# in_out_mcp23017.net
KiCad netlist of a schematic drawn in EAGLE
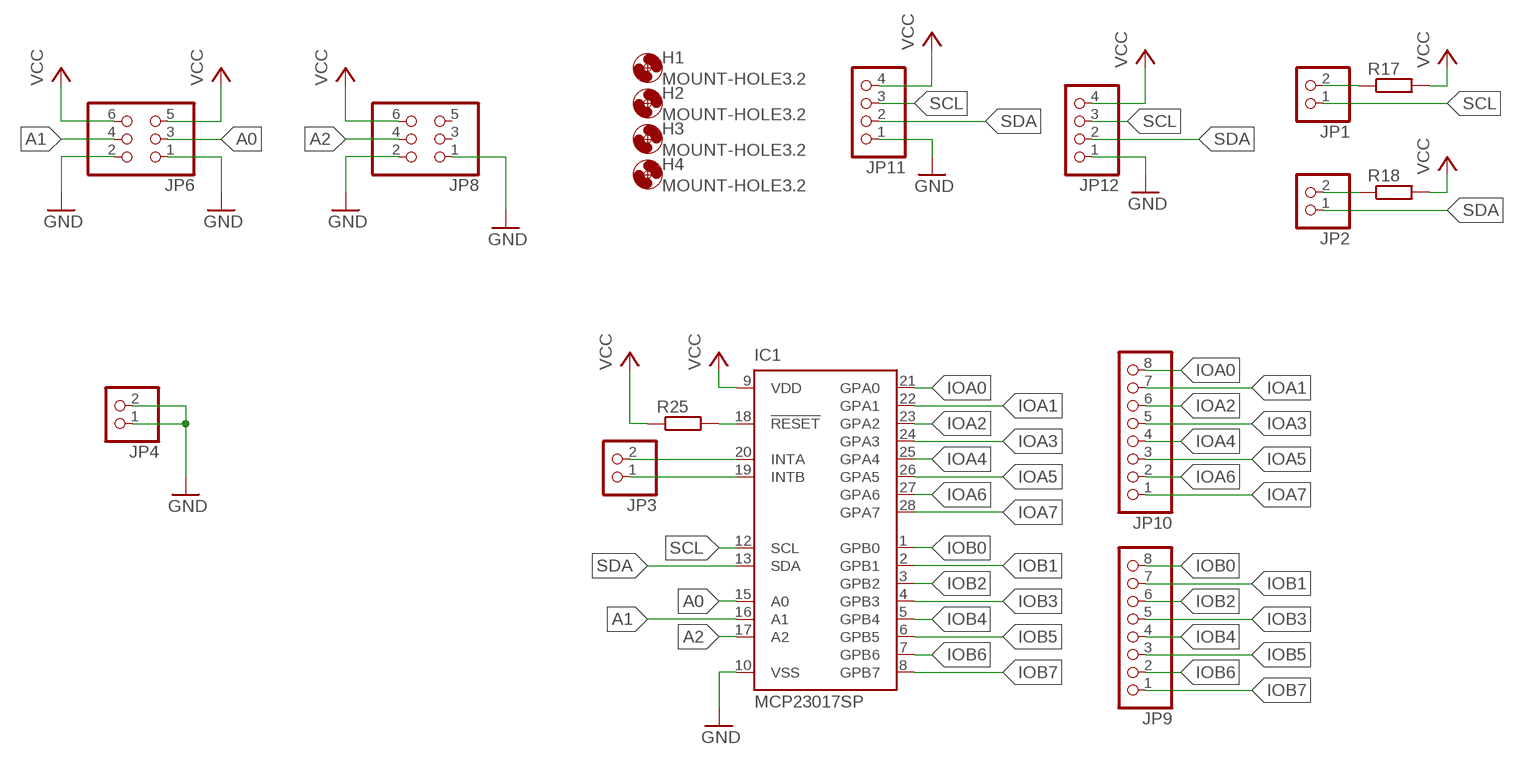
[diagram p0: schematic, sheet 1]

(export (version "E")
  (design (tool "Eeschema 10.0.6"))
  (components
    (comp (ref "H1")
      (value "MOUNT-HOLE3.2")
      (footprint "eagle-import:3,2")
      (libsource (lib "eagle-import") (part "MOUNT-HOLE3.2"))
    )
    (comp (ref "H2")
      (value "MOUNT-HOLE3.2")
      (footprint "eagle-import:3,2")
      (libsource (lib "eagle-import") (part "MOUNT-HOLE3.2"))
    )
    (comp (ref "H3")
      (value "MOUNT-HOLE3.2")
      (footprint "eagle-import:3,2")
      (libsource (lib "eagle-import") (part "MOUNT-HOLE3.2"))
    )
    (comp (ref "H4")
      (value "MOUNT-HOLE3.2")
      (footprint "eagle-import:3,2")
      (libsource (lib "eagle-import") (part "MOUNT-HOLE3.2"))
    )
    (comp (ref "IC1")
      (value "MCP23017SP")
      (footprint "eagle-import:DIL28-3")
      (libsource (lib "eagle-import") (part "MCP23017SP"))
    )
    (comp (ref "JP1")
      (value "PINHD-1X2")
      (footprint "eagle-import:1X02")
      (libsource (lib "eagle-import") (part "PINHD-1X2"))
    )
    (comp (ref "JP2")
      (value "PINHD-1X2")
      (footprint "eagle-import:1X02")
      (libsource (lib "eagle-import") (part "PINHD-1X2"))
    )
    (comp (ref "JP3")
      (value "PINHD-1X2")
      (footprint "eagle-import:1X02")
      (libsource (lib "eagle-import") (part "PINHD-1X2"))
    )
    (comp (ref "JP4")
      (value "PINHD-1X2")
      (footprint "eagle-import:1X02")
      (libsource (lib "eagle-import") (part "PINHD-1X2"))
    )
    (comp (ref "JP6")
      (value "PINHD-2X3")
      (footprint "eagle-import:2X03")
      (libsource (lib "eagle-import") (part "PINHD-2X3"))
    )
    (comp (ref "JP8")
      (value "PINHD-2X3")
      (footprint "eagle-import:2X03")
      (libsource (lib "eagle-import") (part "PINHD-2X3"))
    )
    (comp (ref "JP9")
      (value "PINHD-1X8")
      (footprint "eagle-import:1X08")
      (libsource (lib "eagle-import") (part "PINHD-1X8"))
    )
    (comp (ref "JP10")
      (value "PINHD-1X8")
      (footprint "eagle-import:1X08")
      (libsource (lib "eagle-import") (part "PINHD-1X8"))
    )
    (comp (ref "JP11")
      (value "PINHD-1X4")
      (footprint "eagle-import:1X04")
      (libsource (lib "eagle-import") (part "PINHD-1X4"))
    )
    (comp (ref "JP12")
      (value "PINHD-1X4")
      (footprint "eagle-import:1X04")
      (libsource (lib "eagle-import") (part "PINHD-1X4"))
    )
    (comp (ref "R17")
      (value "R-EU_0207/10")
      (footprint "eagle-import:0207_10")
      (libsource (lib "eagle-import") (part "R-EU_0207/10"))
    )
    (comp (ref "R18")
      (value "R-EU_0207/10")
      (footprint "eagle-import:0207_10")
      (libsource (lib "eagle-import") (part "R-EU_0207/10"))
    )
    (comp (ref "R25")
      (value "R-EU_0207/10")
      (footprint "eagle-import:0207_10")
      (libsource (lib "eagle-import") (part "R-EU_0207/10"))
    )
  )
  (nets
    (net (code "1") (name "A0") (class "Default")
      (node (ref "IC1") (pin "15") (pinfunction "A0_15") (pintype "input"))
      (node (ref "JP6") (pin "3") (pinfunction "3_3") (pintype "passive"))
    )
    (net (code "2") (name "A1") (class "Default")
      (node (ref "IC1") (pin "16") (pinfunction "A1_16") (pintype "input"))
      (node (ref "JP6") (pin "4") (pinfunction "4_4") (pintype "passive"))
    )
    (net (code "3") (name "A2") (class "Default")
      (node (ref "IC1") (pin "17") (pinfunction "A2_17") (pintype "input"))
      (node (ref "JP8") (pin "4") (pinfunction "4_4") (pintype "passive"))
    )
    (net (code "4") (name "GND") (class "Default")
      (node (ref "IC1") (pin "10") (pinfunction "VSS_10") (pintype "power_in"))
      (node (ref "JP11") (pin "1") (pinfunction "1_1") (pintype "passive"))
      (node (ref "JP12") (pin "1") (pinfunction "1_1") (pintype "passive"))
      (node (ref "JP4") (pin "1") (pinfunction "1_1") (pintype "passive"))
      (node (ref "JP4") (pin "2") (pinfunction "2_2") (pintype "passive"))
      (node (ref "JP6") (pin "1") (pinfunction "1_1") (pintype "passive"))
      (node (ref "JP6") (pin "2") (pinfunction "2_2") (pintype "passive"))
      (node (ref "JP8") (pin "1") (pinfunction "1_1") (pintype "passive"))
      (node (ref "JP8") (pin "2") (pinfunction "2_2") (pintype "passive"))
    )
    (net (code "5") (name "IOA0") (class "Default")
      (node (ref "IC1") (pin "21") (pinfunction "GPA0_21") (pintype "bidirectional"))
      (node (ref "JP10") (pin "8") (pinfunction "8_8") (pintype "passive"))
    )
    (net (code "6") (name "IOA1") (class "Default")
      (node (ref "IC1") (pin "22") (pinfunction "GPA1_22") (pintype "bidirectional"))
      (node (ref "JP10") (pin "7") (pinfunction "7_7") (pintype "passive"))
    )
    (net (code "7") (name "IOA2") (class "Default")
      (node (ref "IC1") (pin "23") (pinfunction "GPA2_23") (pintype "bidirectional"))
      (node (ref "JP10") (pin "6") (pinfunction "6_6") (pintype "passive"))
    )
    (net (code "8") (name "IOA3") (class "Default")
      (node (ref "IC1") (pin "24") (pinfunction "GPA3_24") (pintype "bidirectional"))
      (node (ref "JP10") (pin "5") (pinfunction "5_5") (pintype "passive"))
    )
    (net (code "9") (name "IOA4") (class "Default")
      (node (ref "IC1") (pin "25") (pinfunction "GPA4_25") (pintype "bidirectional"))
      (node (ref "JP10") (pin "4") (pinfunction "4_4") (pintype "passive"))
    )
    (net (code "10") (name "IOA5") (class "Default")
      (node (ref "IC1") (pin "26") (pinfunction "GPA5_26") (pintype "bidirectional"))
      (node (ref "JP10") (pin "3") (pinfunction "3_3") (pintype "passive"))
    )
    (net (code "11") (name "IOA6") (class "Default")
      (node (ref "IC1") (pin "27") (pinfunction "GPA6_27") (pintype "bidirectional"))
      (node (ref "JP10") (pin "2") (pinfunction "2_2") (pintype "passive"))
    )
    (net (code "12") (name "IOA7") (class "Default")
      (node (ref "IC1") (pin "28") (pinfunction "GPA7_28") (pintype "bidirectional"))
      (node (ref "JP10") (pin "1") (pinfunction "1_1") (pintype "passive"))
    )
    (net (code "13") (name "IOB0") (class "Default")
      (node (ref "IC1") (pin "1") (pinfunction "GPB0_1") (pintype "bidirectional"))
      (node (ref "JP9") (pin "8") (pinfunction "8_8") (pintype "passive"))
    )
    (net (code "14") (name "IOB1") (class "Default")
      (node (ref "IC1") (pin "2") (pinfunction "GPB1_2") (pintype "bidirectional"))
      (node (ref "JP9") (pin "7") (pinfunction "7_7") (pintype "passive"))
    )
    (net (code "15") (name "IOB2") (class "Default")
      (node (ref "IC1") (pin "3") (pinfunction "GPB2_3") (pintype "bidirectional"))
      (node (ref "JP9") (pin "6") (pinfunction "6_6") (pintype "passive"))
    )
    (net (code "16") (name "IOB3") (class "Default")
      (node (ref "IC1") (pin "4") (pinfunction "GPB3_4") (pintype "bidirectional"))
      (node (ref "JP9") (pin "5") (pinfunction "5_5") (pintype "passive"))
    )
    (net (code "17") (name "IOB4") (class "Default")
      (node (ref "IC1") (pin "5") (pinfunction "GPB4_5") (pintype "bidirectional"))
      (node (ref "JP9") (pin "4") (pinfunction "4_4") (pintype "passive"))
    )
    (net (code "18") (name "IOB5") (class "Default")
      (node (ref "IC1") (pin "6") (pinfunction "GPB5_6") (pintype "bidirectional"))
      (node (ref "JP9") (pin "3") (pinfunction "3_3") (pintype "passive"))
    )
    (net (code "19") (name "IOB6") (class "Default")
      (node (ref "IC1") (pin "7") (pinfunction "GPB6_7") (pintype "bidirectional"))
      (node (ref "JP9") (pin "2") (pinfunction "2_2") (pintype "passive"))
    )
    (net (code "20") (name "IOB7") (class "Default")
      (node (ref "IC1") (pin "8") (pinfunction "GPB7_8") (pintype "bidirectional"))
      (node (ref "JP9") (pin "1") (pinfunction "1_1") (pintype "passive"))
    )
    (net (code "21") (name "Net-(IC1-INTA)") (class "Default")
      (node (ref "IC1") (pin "20") (pinfunction "INTA_20") (pintype "output"))
      (node (ref "JP3") (pin "2") (pinfunction "2_2") (pintype "passive"))
    )
    (net (code "22") (name "Net-(IC1-INTB)") (class "Default")
      (node (ref "IC1") (pin "19") (pinfunction "INTB_19") (pintype "output"))
      (node (ref "JP3") (pin "1") (pinfunction "1_1") (pintype "passive"))
    )
    (net (code "23") (name "Net-(IC1-~{RESET})") (class "Default")
      (node (ref "IC1") (pin "18") (pinfunction "~{RESET}_18") (pintype "input"))
      (node (ref "R25") (pin "2") (pinfunction "2_2") (pintype "passive"))
    )
    (net (code "24") (name "Net-(JP1-Pad2)") (class "Default")
      (node (ref "JP1") (pin "2") (pinfunction "2_2") (pintype "passive"))
      (node (ref "R17") (pin "1") (pinfunction "1_1") (pintype "passive"))
    )
    (net (code "25") (name "Net-(JP2-Pad2)") (class "Default")
      (node (ref "JP2") (pin "2") (pinfunction "2_2") (pintype "passive"))
      (node (ref "R18") (pin "1") (pinfunction "1_1") (pintype "passive"))
    )
    (net (code "26") (name "SCL") (class "Default")
      (node (ref "IC1") (pin "12") (pinfunction "SCL_12") (pintype "input"))
      (node (ref "JP1") (pin "1") (pinfunction "1_1") (pintype "passive"))
      (node (ref "JP11") (pin "3") (pinfunction "3_3") (pintype "passive"))
      (node (ref "JP12") (pin "3") (pinfunction "3_3") (pintype "passive"))
    )
    (net (code "27") (name "SDA") (class "Default")
      (node (ref "IC1") (pin "13") (pinfunction "SDA_13") (pintype "bidirectional"))
      (node (ref "JP11") (pin "2") (pinfunction "2_2") (pintype "passive"))
      (node (ref "JP12") (pin "2") (pinfunction "2_2") (pintype "passive"))
      (node (ref "JP2") (pin "1") (pinfunction "1_1") (pintype "passive"))
    )
    (net (code "28") (name "VCC") (class "Default")
      (node (ref "IC1") (pin "9") (pinfunction "VDD_9") (pintype "power_in"))
      (node (ref "JP11") (pin "4") (pinfunction "4_4") (pintype "passive"))
      (node (ref "JP12") (pin "4") (pinfunction "4_4") (pintype "passive"))
      (node (ref "JP6") (pin "5") (pinfunction "5_5") (pintype "passive"))
      (node (ref "JP6") (pin "6") (pinfunction "6_6") (pintype "passive"))
      (node (ref "JP8") (pin "6") (pinfunction "6_6") (pintype "passive"))
      (node (ref "R17") (pin "2") (pinfunction "2_2") (pintype "passive"))
      (node (ref "R18") (pin "2") (pinfunction "2_2") (pintype "passive"))
      (node (ref "R25") (pin "1") (pinfunction "1_1") (pintype "passive"))
    )
    (net (code "29") (name "unconnected-(JP8-Pad3)") (class "Default")
      (node (ref "JP8") (pin "3") (pinfunction "3_3") (pintype "passive"))
    )
    (net (code "30") (name "unconnected-(JP8-Pad5)") (class "Default")
      (node (ref "JP8") (pin "5") (pinfunction "5_5") (pintype "passive"))
    )
  )
)
